# 3_-_Position2Go_RF_Section.net
KiCad netlist of a schematic drawn in Altium Designer
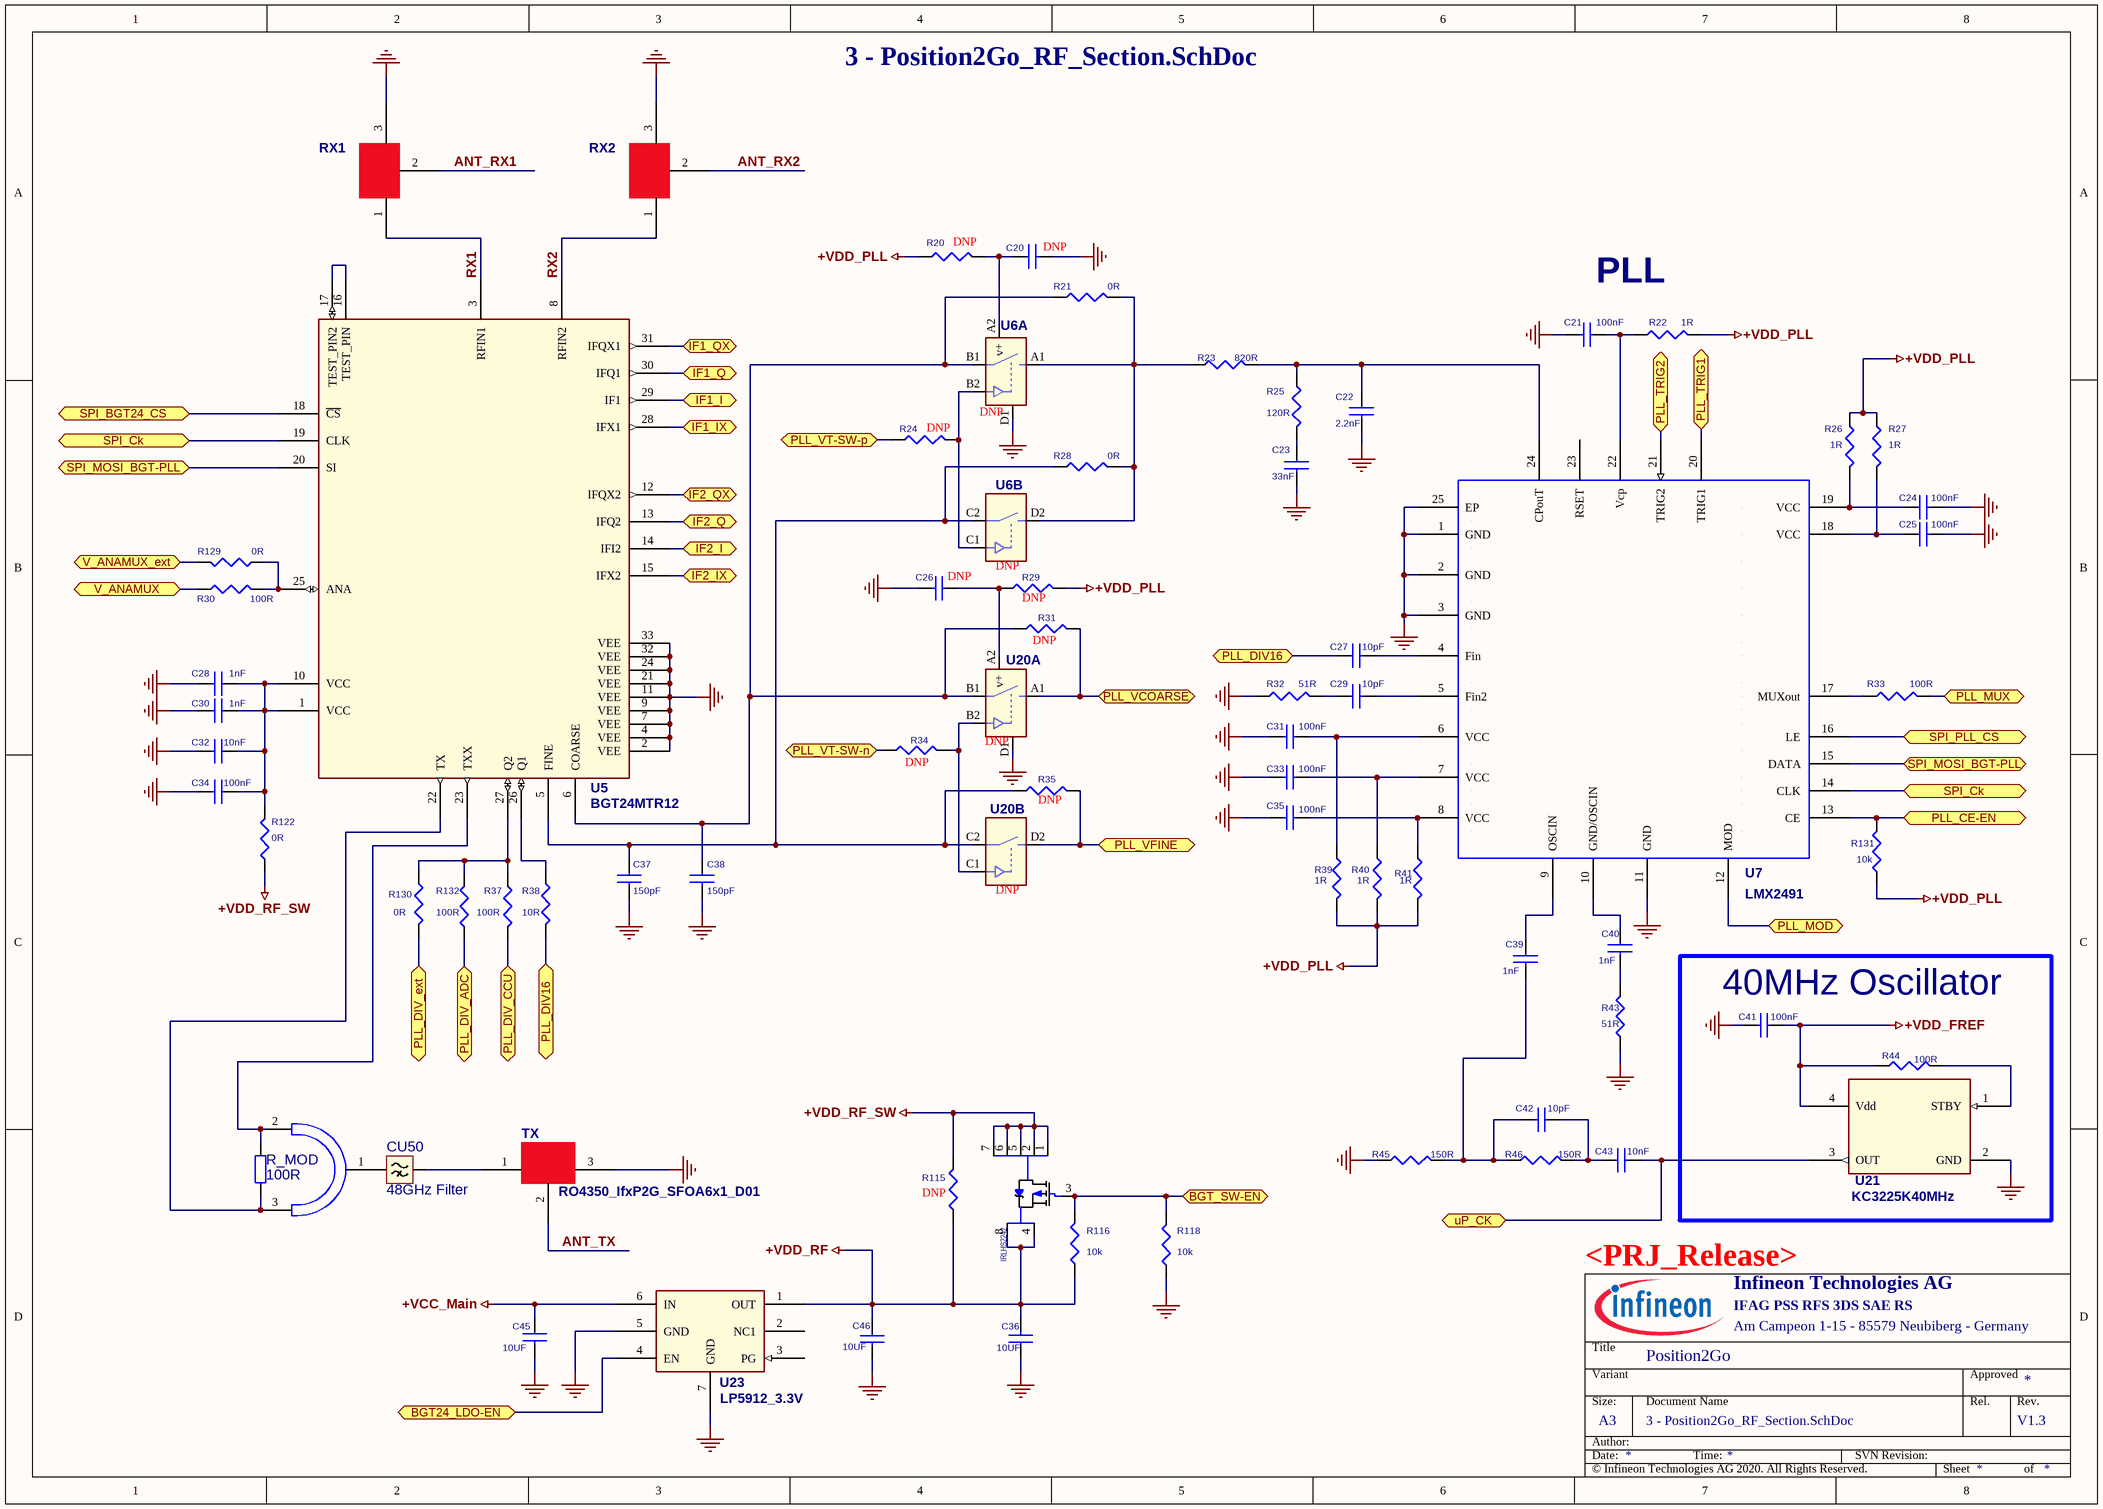
[diagram p0: 3 - Position2Go_RF_Section.SchDoc]

(export (version "E")
  (design (tool "Eeschema 10.0.6"))
  (components
    (comp (ref "C20")
      (value "DNP")
      (footprint "C_0201")
      (description "NB Not Fitted")
      (fields (field (name "VOLTAGE") "50V") (field (name "TOLERANCE") "5%"))
      (libsource (lib "*") (part "100nF_Dup1"))
    )
    (comp (ref "C21")
      (value "100nF")
      (footprint "C_0201")
      (fields (field (name "VOLTAGE") "50V") (field (name "TOLERANCE") "5%"))
      (libsource (lib "*") (part "100nF_Dup1"))
    )
    (comp (ref "C22")
      (value "2.2nF")
      (footprint "0402_durac")
      (fields (field (name "VOLTAGE") "50V") (field (name "TOLERANCE") "5%"))
      (libsource (lib "*") (part "3.9nF"))
    )
    (comp (ref "C23")
      (value "33nF")
      (footprint "0402_durac")
      (fields (field (name "TOLERANCE") "10%") (field (name "VOLTAGE") "50V"))
      (libsource (lib "*") (part "68nF"))
    )
    (comp (ref "C24")
      (value "100nF")
      (footprint "C_0201")
      (fields (field (name "VOLTAGE") "50V") (field (name "TOLERANCE") "5%"))
      (libsource (lib "*") (part "100nF_Dup1"))
    )
    (comp (ref "C25")
      (value "100nF")
      (footprint "C_0201")
      (fields (field (name "VOLTAGE") "50V") (field (name "TOLERANCE") "5%"))
      (libsource (lib "*") (part "100nF_Dup1"))
    )
    (comp (ref "C26")
      (value "DNP")
      (footprint "C_0201")
      (description "NB Not Fitted")
      (fields (field (name "VOLTAGE") "50V") (field (name "TOLERANCE") "5%"))
      (libsource (lib "*") (part "100nF_Dup1"))
    )
    (comp (ref "C27")
      (value "10pF")
      (footprint "C_0201")
      (description "10pF  ±1%  50V  NPO")
      (fields (field (name "VOLTAGE") "50V") (field (name "TOLERANCE") "1%"))
      (libsource (lib "*") (part "10pF"))
    )
    (comp (ref "C28")
      (value "1nF")
      (footprint "C_0201")
      (fields (field (name "TOLERANCE") "10%") (field (name "VOLTAGE") "25V"))
      (libsource (lib "*") (part "1nF"))
    )
    (comp (ref "C29")
      (value "10pF")
      (footprint "C_0201")
      (description "10pF  ±1%  50V  NPO")
      (fields (field (name "VOLTAGE") "50V") (field (name "TOLERANCE") "1%"))
      (libsource (lib "*") (part "10pF"))
    )
    (comp (ref "C30")
      (value "1nF")
      (footprint "C_0201")
      (fields (field (name "TOLERANCE") "10%") (field (name "VOLTAGE") "25V"))
      (libsource (lib "*") (part "1nF"))
    )
    (comp (ref "C31")
      (value "100nF")
      (footprint "C_0201")
      (fields (field (name "VOLTAGE") "50V") (field (name "TOLERANCE") "5%"))
      (libsource (lib "*") (part "100nF_Dup1"))
    )
    (comp (ref "C32")
      (value "10nF")
      (footprint "C_0201")
      (fields (field (name "TOLERANCE") "10%") (field (name "VOLTAGE") "10V"))
      (libsource (lib "*") (part "10nF"))
    )
    (comp (ref "C33")
      (value "100nF")
      (footprint "C_0201")
      (fields (field (name "VOLTAGE") "50V") (field (name "TOLERANCE") "5%"))
      (libsource (lib "*") (part "100nF_Dup1"))
    )
    (comp (ref "C34")
      (value "100nF")
      (footprint "C_0201")
      (fields (field (name "VOLTAGE") "50V") (field (name "TOLERANCE") "5%"))
      (libsource (lib "*") (part "100nF_Dup1"))
    )
    (comp (ref "C35")
      (value "100nF")
      (footprint "C_0201")
      (fields (field (name "VOLTAGE") "50V") (field (name "TOLERANCE") "5%"))
      (libsource (lib "*") (part "100nF_Dup1"))
    )
    (comp (ref "C36")
      (value "10UF")
      (footprint "0402_durac")
      (fields (field (name "TOLERANCE") "20%") (field (name "VOLTAGE") "10V"))
      (libsource (lib "*") (part "10UF"))
    )
    (comp (ref "C37")
      (value "150pF")
      (footprint "C_0201")
      (description "150pF  ±5%  25V  NPO")
      (fields (field (name "TOLERANCE") "5%") (field (name "VOLTAGE") "25V"))
      (libsource (lib "*") (part "100pF"))
    )
    (comp (ref "C38")
      (value "150pF")
      (footprint "C_0201")
      (description "150pF  ±5%  25V  NPO")
      (fields (field (name "TOLERANCE") "5%") (field (name "VOLTAGE") "25V"))
      (libsource (lib "*") (part "100pF"))
    )
    (comp (ref "C39")
      (value "1nF")
      (footprint "C_0201")
      (fields (field (name "TOLERANCE") "10%") (field (name "VOLTAGE") "25V"))
      (libsource (lib "*") (part "1nF"))
    )
    (comp (ref "C40")
      (value "1nF")
      (footprint "C_0201")
      (fields (field (name "TOLERANCE") "10%") (field (name "VOLTAGE") "25V"))
      (libsource (lib "*") (part "1nF"))
    )
    (comp (ref "C41")
      (value "100nF")
      (footprint "C_0201")
      (fields (field (name "VOLTAGE") "50V") (field (name "TOLERANCE") "5%"))
      (libsource (lib "*") (part "100nF_Dup1"))
    )
    (comp (ref "C42")
      (value "10pF")
      (footprint "C_0201")
      (description "10pF  ±1%  50V  NPO")
      (fields (field (name "VOLTAGE") "50V") (field (name "TOLERANCE") "1%"))
      (libsource (lib "*") (part "10pF"))
    )
    (comp (ref "C43")
      (value "10nF")
      (footprint "C_0201")
      (fields (field (name "TOLERANCE") "10%") (field (name "VOLTAGE") "10V"))
      (libsource (lib "*") (part "10nF"))
    )
    (comp (ref "C45")
      (value "10UF")
      (footprint "0402_durac")
      (fields (field (name "TOLERANCE") "20%") (field (name "VOLTAGE") "10V"))
      (libsource (lib "*") (part "10UF"))
    )
    (comp (ref "C46")
      (value "10UF")
      (footprint "0402_durac")
      (fields (field (name "TOLERANCE") "20%") (field (name "VOLTAGE") "10V"))
      (libsource (lib "*") (part "10UF"))
    )
    (comp (ref "CU1")
      (value "Divider")
      (footprint "WILKSON")
      (description "Wilkinson")
      (libsource (lib "523_137_ED01") (part "WILKINSON"))
    )
    (comp (ref "CU50")
      (value "48GHz Filter")
      (footprint "48GHz_Filter")
      (libsource (lib "Infineon_BGT24_RefDesign") (part "48GHz_Filter"))
    )
    (comp (ref "Q1") (value "IRLHS2242") (footprint "IRLSH2242") (libsource (lib "*") (part "IRLHS2242")))
    (comp (ref "R20")
      (value "DNP")
      (footprint "R_0201")
      (description "NB Not Fitted")
      (fields (field (name "TOLERANCE") "1%") (field (name "POWER") "0.063W"))
      (libsource (lib "*") (part "0_Dup2"))
    )
    (comp (ref "R21")
      (value "0R")
      (footprint "R_0201")
      (fields (field (name "TOLERANCE") "1%") (field (name "POWER") "0.063W"))
      (libsource (lib "*") (part "0_Dup2"))
    )
    (comp (ref "R22")
      (value "1R")
      (footprint "R_0201")
      (fields (field (name "POWER") "0.063W") (field (name "TOLERANCE") "1%"))
      (libsource (lib "*") (part "1"))
    )
    (comp (ref "R23")
      (value "820R")
      (footprint "0402_durac")
      (fields (field (name "POWER") "0.063W") (field (name "TOLERANCE") "5%"))
      (libsource (lib "*") (part "0_Dup1"))
    )
    (comp (ref "R24")
      (value "DNP")
      (footprint "R_0201")
      (description "NB Not Fitted")
      (fields (field (name "TOLERANCE") "1%") (field (name "POWER") "0.063W"))
      (libsource (lib "*") (part "100"))
    )
    (comp (ref "R25")
      (value "120R")
      (footprint "0402-A")
      (fields (field (name "POWER") "0.063W") (field (name "TOLERANCE") "1%"))
      (libsource (lib "*") (part "20"))
    )
    (comp (ref "R26")
      (value "1R")
      (footprint "R_0201")
      (fields (field (name "POWER") "0.063W") (field (name "TOLERANCE") "1%"))
      (libsource (lib "*") (part "1"))
    )
    (comp (ref "R27")
      (value "1R")
      (footprint "R_0201")
      (fields (field (name "POWER") "0.063W") (field (name "TOLERANCE") "1%"))
      (libsource (lib "*") (part "1"))
    )
    (comp (ref "R28")
      (value "0R")
      (footprint "R_0201")
      (fields (field (name "TOLERANCE") "1%") (field (name "POWER") "0.063W"))
      (libsource (lib "*") (part "0_Dup2"))
    )
    (comp (ref "R29")
      (value "DNP")
      (footprint "R_0201")
      (description "NB Not Fitted")
      (fields (field (name "TOLERANCE") "1%") (field (name "POWER") "0.063W"))
      (libsource (lib "*") (part "0_Dup2"))
    )
    (comp (ref "R30")
      (value "100R")
      (footprint "R_0201")
      (fields (field (name "TOLERANCE") "1%") (field (name "POWER") "0.063W"))
      (libsource (lib "*") (part "100"))
    )
    (comp (ref "R31")
      (value "DNP")
      (footprint "R_0201")
      (description "NB Not Fitted")
      (fields (field (name "TOLERANCE") "1%") (field (name "POWER") "0.063W"))
      (libsource (lib "*") (part "0_Dup2"))
    )
    (comp (ref "R32")
      (value "51R")
      (footprint "R_0201")
      (fields (field (name "TOLERANCE") "1%") (field (name "POWER") "0.063W"))
      (libsource (lib "*") (part "51"))
    )
    (comp (ref "R33")
      (value "100R")
      (footprint "R_0201")
      (fields (field (name "TOLERANCE") "1%") (field (name "POWER") "0.063W"))
      (libsource (lib "*") (part "100"))
    )
    (comp (ref "R34")
      (value "DNP")
      (footprint "R_0201")
      (description "NB Not Fitted")
      (fields (field (name "TOLERANCE") "1%") (field (name "POWER") "0.063W"))
      (libsource (lib "*") (part "100"))
    )
    (comp (ref "R35")
      (value "DNP")
      (footprint "R_0201")
      (description "NB Not Fitted")
      (fields (field (name "TOLERANCE") "1%") (field (name "POWER") "0.063W"))
      (libsource (lib "*") (part "0_Dup2"))
    )
    (comp (ref "R37")
      (value "100R")
      (footprint "R_0201")
      (fields (field (name "TOLERANCE") "1%") (field (name "POWER") "0.063W"))
      (libsource (lib "*") (part "100"))
    )
    (comp (ref "R38")
      (value "10R")
      (footprint "R_0201")
      (fields (field (name "TOLERANCE") "1%") (field (name "POWER") "0.063W"))
      (libsource (lib "*") (part "10"))
    )
    (comp (ref "R39")
      (value "1R")
      (footprint "R_0201")
      (fields (field (name "POWER") "0.063W") (field (name "TOLERANCE") "1%"))
      (libsource (lib "*") (part "1"))
    )
    (comp (ref "R40")
      (value "1R")
      (footprint "R_0201")
      (fields (field (name "POWER") "0.063W") (field (name "TOLERANCE") "1%"))
      (libsource (lib "*") (part "1"))
    )
    (comp (ref "R41")
      (value "1R")
      (footprint "R_0201")
      (fields (field (name "POWER") "0.063W") (field (name "TOLERANCE") "1%"))
      (libsource (lib "*") (part "1"))
    )
    (comp (ref "R43")
      (value "51R")
      (footprint "R_0201")
      (fields (field (name "TOLERANCE") "1%") (field (name "POWER") "0.063W"))
      (libsource (lib "*") (part "51"))
    )
    (comp (ref "R44")
      (value "100R")
      (footprint "R_0201")
      (fields (field (name "TOLERANCE") "1%") (field (name "POWER") "0.063W"))
      (libsource (lib "*") (part "100"))
    )
    (comp (ref "R45")
      (value "150R")
      (footprint "R_0201")
      (fields (field (name "TOLERANCE") "1%") (field (name "POWER") "0.063W"))
      (libsource (lib "*") (part "150"))
    )
    (comp (ref "R46")
      (value "150R")
      (footprint "R_0201")
      (fields (field (name "TOLERANCE") "1%") (field (name "POWER") "0.063W"))
      (libsource (lib "*") (part "150"))
    )
    (comp (ref "R115")
      (value "DNP")
      (footprint "R_0201")
      (description "NB Not Fitted")
      (fields (field (name "TOLERANCE") "1%") (field (name "POWER") "0.063W"))
      (libsource (lib "*") (part "0_Dup2"))
    )
    (comp (ref "R116")
      (value "10k")
      (footprint "R_0201")
      (fields (field (name "TOLERANCE") "1%") (field (name "POWER") "0.063W"))
      (libsource (lib "*") (part "10K_Dup1"))
    )
    (comp (ref "R118")
      (value "10k")
      (footprint "R_0201")
      (fields (field (name "TOLERANCE") "1%") (field (name "POWER") "0.063W"))
      (libsource (lib "*") (part "10K_Dup1"))
    )
    (comp (ref "R122")
      (value "0R")
      (footprint "0603")
      (description "0R 0603")
      (fields (field (name "TOLERANCE") "1%") (field (name "POWER") "0.125W"))
      (libsource (lib "*") (part "0"))
    )
    (comp (ref "R129")
      (value "0R")
      (footprint "R_0201")
      (fields (field (name "TOLERANCE") "1%") (field (name "POWER") "0.063W"))
      (libsource (lib "*") (part "0_Dup2"))
    )
    (comp (ref "R130")
      (value "0R")
      (footprint "R_0201")
      (fields (field (name "TOLERANCE") "1%") (field (name "POWER") "0.063W"))
      (libsource (lib "*") (part "0_Dup2"))
    )
    (comp (ref "R131")
      (value "10k")
      (footprint "R_0201")
      (fields (field (name "TOLERANCE") "1%") (field (name "POWER") "0.063W"))
      (libsource (lib "*") (part "10K_Dup1"))
    )
    (comp (ref "R132")
      (value "100R")
      (footprint "R_0201")
      (fields (field (name "TOLERANCE") "1%") (field (name "POWER") "0.063W"))
      (libsource (lib "*") (part "100"))
    )
    (comp (ref "RX1")
      (value "RO4350_IfxP2G_SFOA6x1_D01")
      (footprint "RO4350_IfxP2G_SFPA6x1_D01_RX1_L")
      (libsource (lib "Position2Go_R4350_IfxP2G_SFPA6x1") (part "RO4350_IfxP2G_SFOA6x1_D01"))
    )
    (comp (ref "RX2")
      (value "RO4350_IfxP2G_SFOA6x1_D01")
      (footprint "RO4350_IfxP2G_SFPA6x1_D01_RX1")
      (libsource (lib "Position2Go_R4350_IfxP2G_SFPA6x1") (part "RO4350_IfxP2G_SFOA6x1_D01"))
    )
    (comp (ref "R_MOD")
      (value "100R")
      (footprint "24GHZ_Wilkinson_R")
      (description "Resistor")
      (fields (field (name "MANUFACTURER") "Multicomp") (field (name "Comment") "RES-100R-50V-1%-0603"))
      (libsource (lib "altium-import") (part "root_1_WILKINSON_0402_"))
    )
    (comp (ref "TX")
      (value "RO4350_IfxP2G_SFOA6x1_D01")
      (footprint "RO4350_IfxP2G_SFPA6x1_D01_Tx")
      (libsource (lib "") (part "RO4350_IfxP2G_SFOA6x1_D01_1"))
    )
    (comp (ref "U5") (value "BGT24MTR12") (footprint "VQFN32-9") (libsource (lib "*") (part "BGT24ATR12")))
    (comp (ref "U6")
      (value "DNP")
      (footprint "OPA2376_DSBGA")
      (description "NB Not Fitted")
      (libsource (lib "523_137_ED01") (part "TS5A23166_DSBGA"))
    )
    (comp (ref "U7") (value "LMX2491") (footprint "VFQN_24") (libsource (lib "*") (part "LMX2491")))
    (comp (ref "U20")
      (value "DNP")
      (footprint "OPA2376_DSBGA")
      (description "NB Not Fitted")
      (libsource (lib "523_137_ED01") (part "TS5A23166_DSBGA"))
    )
    (comp (ref "U21")
      (value "KC3225K40MHz")
      (footprint "3525_40MHz")
      (libsource (lib "*") (part "K3525_40MHz"))
    )
    (comp (ref "U23")
      (value "LP5912_3.3V")
      (footprint "DRV6_1P6X1")
      (libsource (lib "*") (part "LP5912_3_3V"))
    )
  )
  (nets
    (net (code "1") (name "+VCC_Main") (class "Default")
      (node (ref "C45") (pin "1") (pinfunction "1_1") (pintype "passive"))
      (node (ref "U23") (pin "6") (pinfunction "IN_6") (pintype "passive"))
    )
    (net (code "2") (name "+VDD_FREF") (class "Default")
      (node (ref "C41") (pin "1") (pinfunction "1_1") (pintype "passive"))
      (node (ref "R44") (pin "2") (pinfunction "2_2") (pintype "passive"))
      (node (ref "U21") (pin "4") (pinfunction "Vdd_4") (pintype "passive"))
    )
    (net (code "3") (name "+VDD_PLL") (class "Default")
      (node (ref "R131") (pin "1") (pinfunction "1_1") (pintype "passive"))
      (node (ref "R20") (pin "2") (pinfunction "2_2") (pintype "passive"))
      (node (ref "R22") (pin "2") (pinfunction "2_2") (pintype "passive"))
      (node (ref "R26") (pin "1") (pinfunction "1_1") (pintype "passive"))
      (node (ref "R27") (pin "1") (pinfunction "1_1") (pintype "passive"))
      (node (ref "R29") (pin "2") (pinfunction "2_2") (pintype "passive"))
      (node (ref "R39") (pin "2") (pinfunction "2_2") (pintype "passive"))
      (node (ref "R40") (pin "2") (pinfunction "2_2") (pintype "passive"))
      (node (ref "R41") (pin "2") (pinfunction "2_2") (pintype "passive"))
    )
    (net (code "4") (name "+VDD_RF") (class "Default")
      (node (ref "C36") (pin "2") (pinfunction "2_2") (pintype "passive"))
      (node (ref "C46") (pin "1") (pinfunction "1_1") (pintype "passive"))
      (node (ref "Q1") (pin "4") (pinfunction "source_4") (pintype "power_in"))
      (node (ref "Q1") (pin "8") (pinfunction "source_8") (pintype "power_in"))
      (node (ref "R115") (pin "1") (pinfunction "1_1") (pintype "passive"))
      (node (ref "R116") (pin "1") (pinfunction "1_1") (pintype "passive"))
      (node (ref "U23") (pin "1") (pinfunction "OUT_1") (pintype "passive"))
    )
    (net (code "5") (name "+VDD_RF_SW") (class "Default")
      (node (ref "Q1") (pin "1") (pinfunction "DRAIN_1") (pintype "power_in"))
      (node (ref "Q1") (pin "2") (pinfunction "DRAIN_2") (pintype "power_in"))
      (node (ref "Q1") (pin "5") (pinfunction "DRAIN_5") (pintype "power_in"))
      (node (ref "Q1") (pin "6") (pinfunction "DRAIN_6") (pintype "power_in"))
      (node (ref "Q1") (pin "7") (pinfunction "DRAIN_7") (pintype "power_in"))
      (node (ref "R115") (pin "2") (pinfunction "2_2") (pintype "passive"))
      (node (ref "R122") (pin "1") (pinfunction "1_1") (pintype "passive"))
    )
    (net (code "6") (name "/ANT_RX1") (class "Default")
      (node (ref "RX1") (pin "2") (pinfunction "2_2") (pintype "passive"))
    )
    (net (code "7") (name "/ANT_RX2") (class "Default")
      (node (ref "RX2") (pin "2") (pinfunction "2_2") (pintype "passive"))
    )
    (net (code "8") (name "/ANT_TX") (class "Default")
      (node (ref "TX") (pin "2") (pinfunction "2_2") (pintype "passive"))
    )
    (net (code "9") (name "/BGT24_LDO-EN") (class "Default")
      (node (ref "U23") (pin "4") (pinfunction "EN_4") (pintype "passive"))
    )
    (net (code "10") (name "/BGT_SW-EN") (class "Default")
      (node (ref "Q1") (pin "3") (pinfunction "GATE_3") (pintype "passive"))
      (node (ref "R116") (pin "2") (pinfunction "2_2") (pintype "passive"))
      (node (ref "R118") (pin "2") (pinfunction "2_2") (pintype "passive"))
    )
    (net (code "11") (name "/IF1_I") (class "Default")
      (node (ref "U5") (pin "29") (pinfunction "IF1_29") (pintype "output"))
    )
    (net (code "12") (name "/IF1_IX") (class "Default")
      (node (ref "U5") (pin "28") (pinfunction "IFX1_28") (pintype "output"))
    )
    (net (code "13") (name "/IF1_Q") (class "Default")
      (node (ref "U5") (pin "30") (pinfunction "IFQ1_30") (pintype "output"))
    )
    (net (code "14") (name "/IF1_QX") (class "Default")
      (node (ref "U5") (pin "31") (pinfunction "IFQX1_31") (pintype "output"))
    )
    (net (code "15") (name "/IF2_I") (class "Default")
      (node (ref "U5") (pin "14") (pinfunction "IFI2_14") (pintype "passive"))
    )
    (net (code "16") (name "/IF2_IX") (class "Default")
      (node (ref "U5") (pin "15") (pinfunction "IFX2_15") (pintype "passive"))
    )
    (net (code "17") (name "/IF2_Q") (class "Default")
      (node (ref "U5") (pin "13") (pinfunction "IFQ2_13") (pintype "passive"))
    )
    (net (code "18") (name "/IF2_QX") (class "Default")
      (node (ref "U5") (pin "12") (pinfunction "IFQX2_12") (pintype "output"))
    )
    (net (code "19") (name "/PLL_CE-EN") (class "Default")
      (node (ref "R131") (pin "2") (pinfunction "2_2") (pintype "passive"))
      (node (ref "U7") (pin "13") (pinfunction "CE_13") (pintype "passive"))
    )
    (net (code "20") (name "/PLL_DIV16") (class "Default")
      (node (ref "C27") (pin "1") (pinfunction "1_1") (pintype "passive"))
      (node (ref "R38") (pin "2") (pinfunction "2_2") (pintype "passive"))
    )
    (net (code "21") (name "/PLL_DIV_ADC") (class "Default")
      (node (ref "R132") (pin "1") (pinfunction "1_1") (pintype "passive"))
    )
    (net (code "22") (name "/PLL_DIV_CCU") (class "Default")
      (node (ref "R37") (pin "1") (pinfunction "1_1") (pintype "passive"))
    )
    (net (code "23") (name "/PLL_DIV_ext") (class "Default")
      (node (ref "R130") (pin "2") (pinfunction "2_2") (pintype "passive"))
    )
    (net (code "24") (name "/PLL_MOD") (class "Default")
      (node (ref "U7") (pin "12") (pinfunction "MOD_12") (pintype "passive"))
    )
    (net (code "25") (name "/PLL_MUX") (class "Default")
      (node (ref "R33") (pin "2") (pinfunction "2_2") (pintype "passive"))
    )
    (net (code "26") (name "/PLL_TRIG1") (class "Default")
      (node (ref "U7") (pin "20") (pinfunction "TRIG1_20") (pintype "passive"))
    )
    (net (code "27") (name "/PLL_TRIG2") (class "Default")
      (node (ref "U7") (pin "21") (pinfunction "TRIG2_21") (pintype "input"))
    )
    (net (code "28") (name "/PLL_VCOARSE") (class "Default")
      (node (ref "R31") (pin "2") (pinfunction "2_2") (pintype "passive"))
      (node (ref "U20") (pin "A1") (pinfunction "NO1_A1") (pintype "passive"))
    )
    (net (code "29") (name "/PLL_VFINE") (class "Default")
      (node (ref "R35") (pin "2") (pinfunction "2_2") (pintype "passive"))
      (node (ref "U20") (pin "D2") (pinfunction "NO2_D2") (pintype "passive"))
    )
    (net (code "30") (name "/PLL_VT-SW-n") (class "Default")
      (node (ref "R34") (pin "1") (pinfunction "1_1") (pintype "passive"))
    )
    (net (code "31") (name "/PLL_VT-SW-p") (class "Default")
      (node (ref "R24") (pin "1") (pinfunction "1_1") (pintype "passive"))
    )
    (net (code "32") (name "/RX1") (class "Default")
      (node (ref "RX1") (pin "1") (pinfunction "1_1") (pintype "passive"))
      (node (ref "U5") (pin "3") (pinfunction "RFIN1_3") (pintype "passive"))
    )
    (net (code "33") (name "/RX2") (class "Default")
      (node (ref "RX2") (pin "1") (pinfunction "1_1") (pintype "passive"))
      (node (ref "U5") (pin "8") (pinfunction "RFIN2_8") (pintype "passive"))
    )
    (net (code "34") (name "/SPI_BGT24_CS") (class "Default")
      (node (ref "U5") (pin "18") (pinfunction "~{CS}_18") (pintype "passive"))
    )
    (net (code "35") (name "/SPI_Ck") (class "Default")
      (node (ref "U5") (pin "19") (pinfunction "CLK_19") (pintype "passive"))
      (node (ref "U7") (pin "14") (pinfunction "CLK_14") (pintype "passive"))
    )
    (net (code "36") (name "/SPI_MOSI_BGT-PLL") (class "Default")
      (node (ref "U5") (pin "20") (pinfunction "SI_20") (pintype "passive"))
      (node (ref "U7") (pin "15") (pinfunction "DATA_15") (pintype "passive"))
    )
    (net (code "37") (name "/SPI_PLL_CS") (class "Default")
      (node (ref "U7") (pin "16") (pinfunction "LE_16") (pintype "passive"))
    )
    (net (code "38") (name "/V_ANAMUX") (class "Default")
      (node (ref "R30") (pin "1") (pinfunction "1_1") (pintype "passive"))
    )
    (net (code "39") (name "/V_ANAMUX_ext") (class "Default")
      (node (ref "R129") (pin "2") (pinfunction "2_2") (pintype "passive"))
    )
    (net (code "40") (name "/uP_CK") (class "Default")
      (node (ref "C43") (pin "2") (pinfunction "2_2") (pintype "passive"))
      (node (ref "U21") (pin "3") (pinfunction "OUT_3") (pintype "output"))
    )
    (net (code "41") (name "GND_POWER") (class "Default")
      (node (ref "C20") (pin "2") (pinfunction "2_2") (pintype "passive"))
      (node (ref "C21") (pin "2") (pinfunction "2_2") (pintype "passive"))
      (node (ref "C22") (pin "2") (pinfunction "2_2") (pintype "passive"))
      (node (ref "C23") (pin "2") (pinfunction "2_2") (pintype "passive"))
      (node (ref "C24") (pin "2") (pinfunction "2_2") (pintype "passive"))
      (node (ref "C25") (pin "2") (pinfunction "2_2") (pintype "passive"))
      (node (ref "C26") (pin "2") (pinfunction "2_2") (pintype "passive"))
      (node (ref "C28") (pin "2") (pinfunction "2_2") (pintype "passive"))
      (node (ref "C30") (pin "2") (pinfunction "2_2") (pintype "passive"))
      (node (ref "C31") (pin "2") (pinfunction "2_2") (pintype "passive"))
      (node (ref "C32") (pin "2") (pinfunction "2_2") (pintype "passive"))
      (node (ref "C33") (pin "2") (pinfunction "2_2") (pintype "passive"))
      (node (ref "C34") (pin "2") (pinfunction "2_2") (pintype "passive"))
      (node (ref "C35") (pin "2") (pinfunction "2_2") (pintype "passive"))
      (node (ref "C36") (pin "1") (pinfunction "1_1") (pintype "passive"))
      (node (ref "C37") (pin "2") (pinfunction "2_2") (pintype "passive"))
      (node (ref "C38") (pin "2") (pinfunction "2_2") (pintype "passive"))
      (node (ref "C41") (pin "2") (pinfunction "2_2") (pintype "passive"))
      (node (ref "C45") (pin "2") (pinfunction "2_2") (pintype "passive"))
      (node (ref "C46") (pin "2") (pinfunction "2_2") (pintype "passive"))
      (node (ref "R118") (pin "1") (pinfunction "1_1") (pintype "passive"))
      (node (ref "R32") (pin "1") (pinfunction "1_1") (pintype "passive"))
      (node (ref "R43") (pin "1") (pinfunction "1_1") (pintype "passive"))
      (node (ref "R45") (pin "2") (pinfunction "2_2") (pintype "passive"))
      (node (ref "RX1") (pin "3") (pinfunction "3_3") (pintype "passive"))
      (node (ref "RX2") (pin "3") (pinfunction "3_3") (pintype "passive"))
      (node (ref "TX") (pin "3") (pinfunction "3_3") (pintype "passive"))
      (node (ref "U20") (pin "D1") (pinfunction "GND_D1") (pintype "power_in"))
      (node (ref "U21") (pin "2") (pinfunction "GND_2") (pintype "power_in"))
      (node (ref "U23") (pin "5") (pinfunction "GND_5") (pintype "power_in"))
      (node (ref "U23") (pin "7") (pinfunction "GND_7") (pintype "power_in"))
      (node (ref "U5") (pin "11") (pinfunction "VEE_11") (pintype "power_in"))
      (node (ref "U5") (pin "2") (pinfunction "VEE_2") (pintype "power_in"))
      (node (ref "U5") (pin "21") (pinfunction "VEE_21") (pintype "power_in"))
      (node (ref "U5") (pin "24") (pinfunction "VEE_24") (pintype "power_in"))
      (node (ref "U5") (pin "32") (pinfunction "VEE_32") (pintype "power_in"))
      (node (ref "U5") (pin "33") (pinfunction "VEE_33") (pintype "power_in"))
      (node (ref "U5") (pin "4") (pinfunction "VEE_4") (pintype "power_in"))
      (node (ref "U5") (pin "7") (pinfunction "VEE_7") (pintype "power_in"))
      (node (ref "U5") (pin "9") (pinfunction "VEE_9") (pintype "power_in"))
      (node (ref "U6") (pin "D1") (pinfunction "GND_D1") (pintype "power_in"))
      (node (ref "U7") (pin "1") (pinfunction "GND_1") (pintype "power_in"))
      (node (ref "U7") (pin "11") (pinfunction "GND_11") (pintype "power_in"))
      (node (ref "U7") (pin "2") (pinfunction "GND_2") (pintype "power_in"))
      (node (ref "U7") (pin "25") (pinfunction "EP_25") (pintype "passive"))
      (node (ref "U7") (pin "3") (pinfunction "GND_3") (pintype "power_in"))
    )
    (net (code "42") (name "Net-(C23-Pad1)") (class "Default")
      (node (ref "C23") (pin "1") (pinfunction "1_1") (pintype "passive"))
      (node (ref "R25") (pin "2") (pinfunction "2_2") (pintype "passive"))
    )
    (net (code "43") (name "Net-(C24-Pad1)") (class "Default")
      (node (ref "C24") (pin "1") (pinfunction "1_1") (pintype "passive"))
      (node (ref "R26") (pin "2") (pinfunction "2_2") (pintype "passive"))
      (node (ref "U7") (pin "19") (pinfunction "VCC_19") (pintype "power_in"))
    )
    (net (code "44") (name "Net-(C25-Pad1)") (class "Default")
      (node (ref "C25") (pin "1") (pinfunction "1_1") (pintype "passive"))
      (node (ref "R27") (pin "2") (pinfunction "2_2") (pintype "passive"))
      (node (ref "U7") (pin "18") (pinfunction "VCC_18") (pintype "power_in"))
    )
    (net (code "45") (name "Net-(C28-Pad1)") (class "Default")
      (node (ref "C28") (pin "1") (pinfunction "1_1") (pintype "passive"))
      (node (ref "C30") (pin "1") (pinfunction "1_1") (pintype "passive"))
      (node (ref "C32") (pin "1") (pinfunction "1_1") (pintype "passive"))
      (node (ref "C34") (pin "1") (pinfunction "1_1") (pintype "passive"))
      (node (ref "R122") (pin "2") (pinfunction "2_2") (pintype "passive"))
      (node (ref "U5") (pin "1") (pinfunction "VCC_1") (pintype "power_in"))
      (node (ref "U5") (pin "10") (pinfunction "VCC_10") (pintype "power_in"))
    )
    (net (code "46") (name "Net-(C29-Pad1)") (class "Default")
      (node (ref "C29") (pin "1") (pinfunction "1_1") (pintype "passive"))
      (node (ref "R32") (pin "2") (pinfunction "2_2") (pintype "passive"))
    )
    (net (code "47") (name "Net-(C31-Pad1)") (class "Default")
      (node (ref "C31") (pin "1") (pinfunction "1_1") (pintype "passive"))
      (node (ref "R39") (pin "1") (pinfunction "1_1") (pintype "passive"))
      (node (ref "U7") (pin "6") (pinfunction "VCC_6") (pintype "power_in"))
    )
    (net (code "48") (name "Net-(C33-Pad1)") (class "Default")
      (node (ref "C33") (pin "1") (pinfunction "1_1") (pintype "passive"))
      (node (ref "R40") (pin "1") (pinfunction "1_1") (pintype "passive"))
      (node (ref "U7") (pin "7") (pinfunction "VCC_7") (pintype "power_in"))
    )
    (net (code "49") (name "Net-(C35-Pad1)") (class "Default")
      (node (ref "C35") (pin "1") (pinfunction "1_1") (pintype "passive"))
      (node (ref "R41") (pin "1") (pinfunction "1_1") (pintype "passive"))
      (node (ref "U7") (pin "8") (pinfunction "VCC_8") (pintype "power_in"))
    )
    (net (code "50") (name "Net-(C39-Pad2)") (class "Default")
      (node (ref "C39") (pin "2") (pinfunction "2_2") (pintype "passive"))
      (node (ref "C42") (pin "2") (pinfunction "2_2") (pintype "passive"))
      (node (ref "R45") (pin "1") (pinfunction "1_1") (pintype "passive"))
      (node (ref "R46") (pin "2") (pinfunction "2_2") (pintype "passive"))
    )
    (net (code "51") (name "Net-(C40-Pad2)") (class "Default")
      (node (ref "C40") (pin "2") (pinfunction "2_2") (pintype "passive"))
      (node (ref "R43") (pin "2") (pinfunction "2_2") (pintype "passive"))
    )
    (net (code "52") (name "Net-(C42-Pad1)") (class "Default")
      (node (ref "C42") (pin "1") (pinfunction "1_1") (pintype "passive"))
      (node (ref "C43") (pin "1") (pinfunction "1_1") (pintype "passive"))
      (node (ref "R46") (pin "1") (pinfunction "1_1") (pintype "passive"))
    )
    (net (code "53") (name "Net-(CU1-P1)") (class "Default")
      (node (ref "CU1") (pin "1") (pinfunction "P1_1") (pintype "passive"))
      (node (ref "CU50") (pin "2") (pinfunction "2_2") (pintype "passive"))
    )
    (net (code "54") (name "Net-(CU1-P2)") (class "Default")
      (node (ref "CU1") (pin "2") (pinfunction "P2_2") (pintype "passive"))
      (node (ref "R_MOD") (pin "1") (pinfunction "P1_1") (pintype "passive"))
      (node (ref "U5") (pin "23") (pinfunction "TXX_23") (pintype "output"))
    )
    (net (code "55") (name "Net-(CU1-P3)") (class "Default")
      (node (ref "CU1") (pin "3") (pinfunction "P3_3") (pintype "passive"))
      (node (ref "R_MOD") (pin "2") (pinfunction "P2_2") (pintype "passive"))
      (node (ref "U5") (pin "22") (pinfunction "TX_22") (pintype "output"))
    )
    (net (code "56") (name "Net-(CU50-Pad1)") (class "Default")
      (node (ref "CU50") (pin "1") (pinfunction "1_1") (pintype "passive"))
      (node (ref "TX") (pin "1") (pinfunction "1_1") (pintype "passive"))
    )
    (net (code "57") (name "Net-(U5-ANA)") (class "Default")
      (node (ref "R129") (pin "1") (pinfunction "1_1") (pintype "passive"))
      (node (ref "R30") (pin "2") (pinfunction "2_2") (pintype "passive"))
      (node (ref "U5") (pin "25") (pinfunction "ANA_25") (pintype "bidirectional"))
    )
    (net (code "58") (name "Net-(U5-Q1)") (class "Default")
      (node (ref "R38") (pin "1") (pinfunction "1_1") (pintype "passive"))
      (node (ref "U5") (pin "26") (pinfunction "Q1_26") (pintype "bidirectional"))
    )
    (net (code "59") (name "Net-(U5-Q2)") (class "Default")
      (node (ref "R130") (pin "1") (pinfunction "1_1") (pintype "passive"))
      (node (ref "R132") (pin "2") (pinfunction "2_2") (pintype "passive"))
      (node (ref "R37") (pin "2") (pinfunction "2_2") (pintype "passive"))
      (node (ref "U5") (pin "27") (pinfunction "Q2_27") (pintype "bidirectional"))
    )
    (net (code "60") (name "Net-(U5-TEST_PIN)") (class "Default")
      (node (ref "U5") (pin "16") (pinfunction "TEST_PIN_16") (pintype "passive"))
      (node (ref "U5") (pin "17") (pinfunction "TEST_PIN2_17") (pintype "bidirectional"))
    )
    (net (code "61") (name "Net-(U6A-IN1)") (class "Default")
      (node (ref "R24") (pin "2") (pinfunction "2_2") (pintype "passive"))
      (node (ref "U6") (pin "B2") (pinfunction "IN1_B2") (pintype "passive"))
      (node (ref "U6") (pin "C1") (pinfunction "IN2_C1") (pintype "passive"))
    )
    (net (code "62") (name "Net-(U6A-NO1)") (class "Default")
      (node (ref "R21") (pin "2") (pinfunction "2_2") (pintype "passive"))
      (node (ref "R23") (pin "1") (pinfunction "1_1") (pintype "passive"))
      (node (ref "R28") (pin "2") (pinfunction "2_2") (pintype "passive"))
      (node (ref "U6") (pin "A1") (pinfunction "NO1_A1") (pintype "passive"))
      (node (ref "U6") (pin "D2") (pinfunction "NO2_D2") (pintype "passive"))
    )
    (net (code "63") (name "Net-(U6A-v+)") (class "Default")
      (node (ref "C20") (pin "1") (pinfunction "1_1") (pintype "passive"))
      (node (ref "R20") (pin "1") (pinfunction "1_1") (pintype "passive"))
      (node (ref "U6") (pin "A2") (pinfunction "v+_A2") (pintype "power_in"))
    )
    (net (code "64") (name "Net-(U7-CPouT)") (class "Default")
      (node (ref "C22") (pin "1") (pinfunction "1_1") (pintype "passive"))
      (node (ref "R23") (pin "2") (pinfunction "2_2") (pintype "passive"))
      (node (ref "R25") (pin "1") (pinfunction "1_1") (pintype "passive"))
      (node (ref "U7") (pin "24") (pinfunction "CPouT_24") (pintype "passive"))
    )
    (net (code "65") (name "Net-(U7-Fin)") (class "Default")
      (node (ref "C27") (pin "2") (pinfunction "2_2") (pintype "passive"))
      (node (ref "U7") (pin "4") (pinfunction "Fin_4") (pintype "passive"))
    )
    (net (code "66") (name "Net-(U7-Fin2)") (class "Default")
      (node (ref "C29") (pin "2") (pinfunction "2_2") (pintype "passive"))
      (node (ref "U7") (pin "5") (pinfunction "Fin2_5") (pintype "passive"))
    )
    (net (code "67") (name "Net-(U7-GND{slash}OSCIN)") (class "Default")
      (node (ref "C40") (pin "1") (pinfunction "1_1") (pintype "passive"))
      (node (ref "U7") (pin "10") (pinfunction "GND/OSCIN_10") (pintype "passive"))
    )
    (net (code "68") (name "Net-(U7-MUXout)") (class "Default")
      (node (ref "R33") (pin "1") (pinfunction "1_1") (pintype "passive"))
      (node (ref "U7") (pin "17") (pinfunction "MUXout_17") (pintype "power_in"))
    )
    (net (code "69") (name "Net-(U7-OSCIN)") (class "Default")
      (node (ref "C39") (pin "1") (pinfunction "1_1") (pintype "passive"))
      (node (ref "U7") (pin "9") (pinfunction "OSCIN_9") (pintype "passive"))
    )
    (net (code "70") (name "Net-(U7-Vcp)") (class "Default")
      (node (ref "C21") (pin "1") (pinfunction "1_1") (pintype "passive"))
      (node (ref "R22") (pin "1") (pinfunction "1_1") (pintype "passive"))
      (node (ref "U7") (pin "22") (pinfunction "Vcp_22") (pintype "power_in"))
    )
    (net (code "71") (name "Net-(U20A-COM1)") (class "Default")
      (node (ref "C38") (pin "1") (pinfunction "1_1") (pintype "passive"))
      (node (ref "R21") (pin "1") (pinfunction "1_1") (pintype "passive"))
      (node (ref "R31") (pin "1") (pinfunction "1_1") (pintype "passive"))
      (node (ref "U20") (pin "B1") (pinfunction "COM1_B1") (pintype "passive"))
      (node (ref "U5") (pin "6") (pinfunction "COARSE_6") (pintype "passive"))
      (node (ref "U6") (pin "B1") (pinfunction "COM1_B1") (pintype "passive"))
    )
    (net (code "72") (name "Net-(U20A-IN1)") (class "Default")
      (node (ref "R34") (pin "2") (pinfunction "2_2") (pintype "passive"))
      (node (ref "U20") (pin "B2") (pinfunction "IN1_B2") (pintype "passive"))
      (node (ref "U20") (pin "C1") (pinfunction "IN2_C1") (pintype "passive"))
    )
    (net (code "73") (name "Net-(U20A-v+)") (class "Default")
      (node (ref "C26") (pin "1") (pinfunction "1_1") (pintype "passive"))
      (node (ref "R29") (pin "1") (pinfunction "1_1") (pintype "passive"))
      (node (ref "U20") (pin "A2") (pinfunction "v+_A2") (pintype "power_in"))
    )
    (net (code "74") (name "Net-(U20B-COM2)") (class "Default")
      (node (ref "C37") (pin "1") (pinfunction "1_1") (pintype "passive"))
      (node (ref "R28") (pin "1") (pinfunction "1_1") (pintype "passive"))
      (node (ref "R35") (pin "1") (pinfunction "1_1") (pintype "passive"))
      (node (ref "U20") (pin "C2") (pinfunction "COM2_C2") (pintype "passive"))
      (node (ref "U5") (pin "5") (pinfunction "FINE_5") (pintype "passive"))
      (node (ref "U6") (pin "C2") (pinfunction "COM2_C2") (pintype "passive"))
    )
    (net (code "75") (name "Net-(U21-STBY)") (class "Default")
      (node (ref "R44") (pin "1") (pinfunction "1_1") (pintype "passive"))
      (node (ref "U21") (pin "1") (pinfunction "STBY_1") (pintype "input"))
    )
    (net (code "76") (name "unconnected-(U7-RSET-Pad23)") (class "Default")
      (node (ref "U7") (pin "23") (pinfunction "RSET_23") (pintype "passive"))
    )
    (net (code "77") (name "unconnected-(U23-NC1-Pad2)") (class "Default")
      (node (ref "U23") (pin "2") (pinfunction "NC1_2") (pintype "passive"))
    )
    (net (code "78") (name "unconnected-(U23-PG-Pad3)") (class "Default")
      (node (ref "U23") (pin "3") (pinfunction "PG_3") (pintype "input"))
    )
  )
)
